# DAC_Board_TOP.net
KiCad netlist of a schematic drawn in Altium Designer
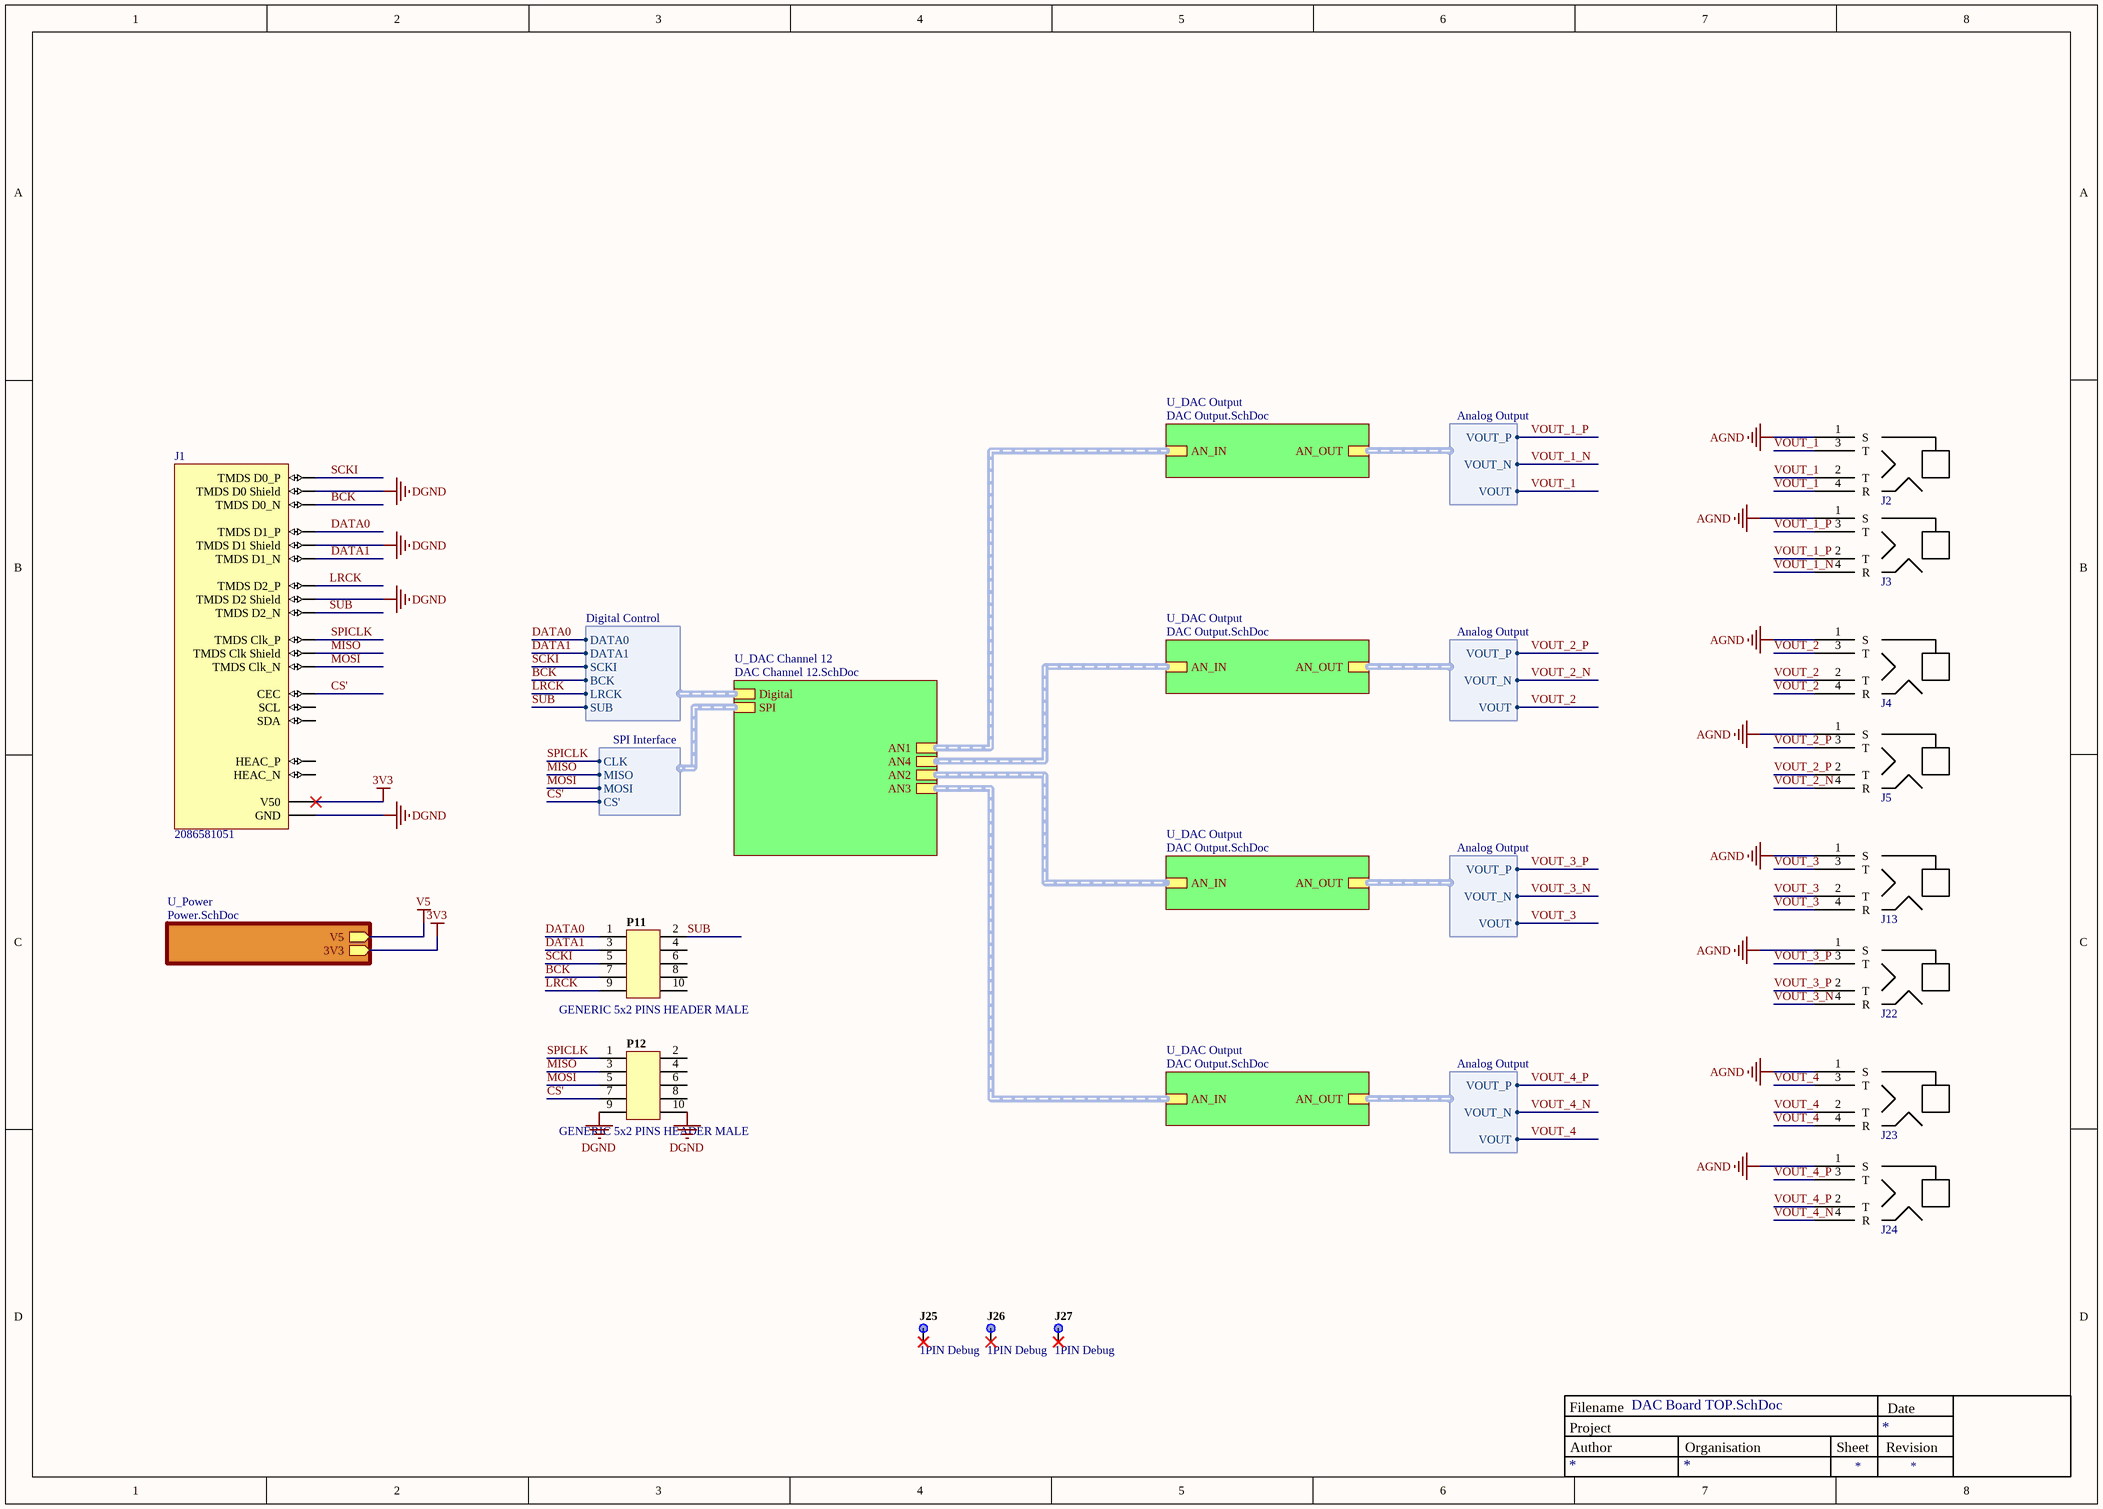
[diagram p0: DAC Board TOP.SchDoc]

(export (version "E")
  (design (tool "Eeschema 10.0.6"))
  (components
    (comp (ref "J1")
      (value "2086581051")
      (footprint "2086581051")
      (description "CONN FEM SMD 19 90Deg HDMI")
      (fields (field (name "DESIGN ITEM ID") "2086581051") (field (name "MANUFACTURER") "Molex"))
      (libsource (lib "University of Malta - MEMENTO") (part "Symbol"))
    )
    (comp (ref "J2")
      (value "SJ1-2503A")
      (footprint "SJ1-2503A-Footprint-1")
      (description "CONN JACK STEREO 2.5MM R/A")
      (libsource (lib "University of Malta - MEMENTO") (part "SJ1-2503A"))
    )
    (comp (ref "J3")
      (value "SJ1-2503A")
      (footprint "SJ1-2503A-Footprint-1")
      (description "CONN JACK STEREO 2.5MM R/A")
      (libsource (lib "University of Malta - MEMENTO") (part "SJ1-2503A"))
    )
    (comp (ref "J4")
      (value "SJ1-2503A")
      (footprint "SJ1-2503A-Footprint-1")
      (description "CONN JACK STEREO 2.5MM R/A")
      (libsource (lib "University of Malta - MEMENTO") (part "SJ1-2503A"))
    )
    (comp (ref "J5")
      (value "SJ1-2503A")
      (footprint "SJ1-2503A-Footprint-1")
      (description "CONN JACK STEREO 2.5MM R/A")
      (libsource (lib "University of Malta - MEMENTO") (part "SJ1-2503A"))
    )
    (comp (ref "J13")
      (value "SJ1-2503A")
      (footprint "SJ1-2503A-Footprint-1")
      (description "CONN JACK STEREO 2.5MM R/A")
      (libsource (lib "University of Malta - MEMENTO") (part "SJ1-2503A"))
    )
    (comp (ref "J22")
      (value "SJ1-2503A")
      (footprint "SJ1-2503A-Footprint-1")
      (description "CONN JACK STEREO 2.5MM R/A")
      (libsource (lib "University of Malta - MEMENTO") (part "SJ1-2503A"))
    )
    (comp (ref "J23")
      (value "SJ1-2503A")
      (footprint "SJ1-2503A-Footprint-1")
      (description "CONN JACK STEREO 2.5MM R/A")
      (libsource (lib "University of Malta - MEMENTO") (part "SJ1-2503A"))
    )
    (comp (ref "J24")
      (value "SJ1-2503A")
      (footprint "SJ1-2503A-Footprint-1")
      (description "CONN JACK STEREO 2.5MM R/A")
      (libsource (lib "University of Malta - MEMENTO") (part "SJ1-2503A"))
    )
    (comp (ref "J25")
      (value "1PIN Debug")
      (footprint "1 Pin Debug Port 0.9mm")
      (description "CONN MAL TH 1 0Deg HEADER")
      (fields (field (name "DESIGN ITEM ID") "1PIN Debug"))
      (libsource (lib "University of Malta - MEMENTO") (part "1PIN Debug"))
    )
    (comp (ref "J26")
      (value "1PIN Debug")
      (footprint "1 Pin Debug Port 0.9mm")
      (description "CONN MAL TH 1 0Deg HEADER")
      (fields (field (name "DESIGN ITEM ID") "1PIN Debug"))
      (libsource (lib "University of Malta - MEMENTO") (part "1PIN Debug"))
    )
    (comp (ref "J27")
      (value "1PIN Debug")
      (footprint "1 Pin Debug Port 0.9mm")
      (description "CONN MAL TH 1 0Deg HEADER")
      (fields (field (name "DESIGN ITEM ID") "1PIN Debug"))
      (libsource (lib "University of Malta - MEMENTO") (part "1PIN Debug"))
    )
    (comp (ref "P11")
      (value "GENERIC 5x2 PINS HEADER MALE")
      (footprint "GENERIC 5PIN 2ROW HEADER 0")
      (description "CONN MAL TH 5x2 0Deg HEADER")
      (fields
        (field (name "DESIGN ITEM ID") "GENERIC 5x2 PINS HEADER MALE")
        (field (name "MANUFACTURER") "Generic")
      )
      (libsource (lib "University of Malta - MEMENTO") (part "GENERIC 5x2 PINS HEADER MALE"))
    )
    (comp (ref "P12")
      (value "GENERIC 5x2 PINS HEADER MALE")
      (footprint "GENERIC 5PIN 2ROW HEADER 0")
      (description "CONN MAL TH 5x2 0Deg HEADER")
      (fields
        (field (name "DESIGN ITEM ID") "GENERIC 5x2 PINS HEADER MALE")
        (field (name "MANUFACTURER") "Generic")
      )
      (libsource (lib "University of Malta - MEMENTO") (part "GENERIC 5x2 PINS HEADER MALE"))
    )
  )
  (nets
    (net (code "11") (name "/BCK") (class "Default")
      (node (ref "J1") (pin "9") (pinfunction "TMDS_D0_N_9") (pintype "bidirectional"))
      (node (ref "P11") (pin "7") (pinfunction "7_7") (pintype "passive"))
    )
    (net (code "12") (name "/CS'") (class "Default")
      (node (ref "J1") (pin "13") (pinfunction "CEC_13") (pintype "bidirectional"))
      (node (ref "P12") (pin "7") (pinfunction "7_7") (pintype "passive"))
    )
    (net (code "13") (name "/DATA0") (class "Default")
      (node (ref "J1") (pin "4") (pinfunction "TMDS_D1_P_4") (pintype "bidirectional"))
      (node (ref "P11") (pin "1") (pinfunction "1_1") (pintype "passive"))
    )
    (net (code "14") (name "/DATA1") (class "Default")
      (node (ref "J1") (pin "6") (pinfunction "TMDS_D1_N_6") (pintype "bidirectional"))
      (node (ref "P11") (pin "3") (pinfunction "3_3") (pintype "passive"))
    )
    (net (code "15") (name "/LRCK") (class "Default")
      (node (ref "J1") (pin "1") (pinfunction "TMDS_D2_P_1") (pintype "bidirectional"))
      (node (ref "P11") (pin "9") (pinfunction "9_9") (pintype "passive"))
    )
    (net (code "16") (name "/MISO") (class "Default")
      (node (ref "J1") (pin "11") (pinfunction "TMDS_Clk_Shield_11") (pintype "bidirectional"))
      (node (ref "P12") (pin "3") (pinfunction "3_3") (pintype "passive"))
    )
    (net (code "17") (name "/MOSI") (class "Default")
      (node (ref "J1") (pin "12") (pinfunction "TMDS_Clk_N_12") (pintype "bidirectional"))
      (node (ref "P12") (pin "5") (pinfunction "5_5") (pintype "passive"))
    )
    (net (code "18") (name "/SCKI") (class "Default")
      (node (ref "J1") (pin "7") (pinfunction "TMDS_D0_P_7") (pintype "bidirectional"))
      (node (ref "P11") (pin "5") (pinfunction "5_5") (pintype "passive"))
    )
    (net (code "19") (name "/SPICLK") (class "Default")
      (node (ref "J1") (pin "10") (pinfunction "TMDS_Clk_P_10") (pintype "bidirectional"))
      (node (ref "P12") (pin "1") (pinfunction "1_1") (pintype "passive"))
    )
    (net (code "20") (name "/SUB") (class "Default")
      (node (ref "J1") (pin "3") (pinfunction "TMDS_D2_N_3") (pintype "bidirectional"))
      (node (ref "P11") (pin "2") (pinfunction "2_2") (pintype "passive"))
    )
    (net (code "21") (name "/VOUT_1") (class "Default")
      (node (ref "J2") (pin "2") (pinfunction "T_2") (pintype "passive"))
      (node (ref "J2") (pin "3") (pinfunction "T_3") (pintype "passive"))
      (node (ref "J2") (pin "4") (pinfunction "R_4") (pintype "passive"))
    )
    (net (code "22") (name "/VOUT_1_N") (class "Default")
      (node (ref "J3") (pin "4") (pinfunction "R_4") (pintype "passive"))
    )
    (net (code "23") (name "/VOUT_1_P") (class "Default")
      (node (ref "J3") (pin "2") (pinfunction "T_2") (pintype "passive"))
      (node (ref "J3") (pin "3") (pinfunction "T_3") (pintype "passive"))
    )
    (net (code "24") (name "/VOUT_2") (class "Default")
      (node (ref "J4") (pin "2") (pinfunction "T_2") (pintype "passive"))
      (node (ref "J4") (pin "3") (pinfunction "T_3") (pintype "passive"))
      (node (ref "J4") (pin "4") (pinfunction "R_4") (pintype "passive"))
    )
    (net (code "25") (name "/VOUT_2_N") (class "Default")
      (node (ref "J5") (pin "4") (pinfunction "R_4") (pintype "passive"))
    )
    (net (code "26") (name "/VOUT_2_P") (class "Default")
      (node (ref "J5") (pin "2") (pinfunction "T_2") (pintype "passive"))
      (node (ref "J5") (pin "3") (pinfunction "T_3") (pintype "passive"))
    )
    (net (code "27") (name "/VOUT_3") (class "Default")
      (node (ref "J13") (pin "2") (pinfunction "T_2") (pintype "passive"))
      (node (ref "J13") (pin "3") (pinfunction "T_3") (pintype "passive"))
      (node (ref "J13") (pin "4") (pinfunction "R_4") (pintype "passive"))
    )
    (net (code "28") (name "/VOUT_3_N") (class "Default")
      (node (ref "J22") (pin "4") (pinfunction "R_4") (pintype "passive"))
    )
    (net (code "29") (name "/VOUT_3_P") (class "Default")
      (node (ref "J22") (pin "2") (pinfunction "T_2") (pintype "passive"))
      (node (ref "J22") (pin "3") (pinfunction "T_3") (pintype "passive"))
    )
    (net (code "30") (name "/VOUT_4") (class "Default")
      (node (ref "J23") (pin "2") (pinfunction "T_2") (pintype "passive"))
      (node (ref "J23") (pin "3") (pinfunction "T_3") (pintype "passive"))
      (node (ref "J23") (pin "4") (pinfunction "R_4") (pintype "passive"))
    )
    (net (code "31") (name "/VOUT_4_N") (class "Default")
      (node (ref "J24") (pin "4") (pinfunction "R_4") (pintype "passive"))
    )
    (net (code "32") (name "/VOUT_4_P") (class "Default")
      (node (ref "J24") (pin "2") (pinfunction "T_2") (pintype "passive"))
      (node (ref "J24") (pin "3") (pinfunction "T_3") (pintype "passive"))
    )
    (net (code "36") (name "3V3") (class "Default")
      (node (ref "J1") (pin "18") (pinfunction "V50_18") (pintype "power_in"))
    )
    (net (code "37") (name "AGND") (class "Default")
      (node (ref "J13") (pin "1") (pinfunction "S_1") (pintype "passive"))
      (node (ref "J2") (pin "1") (pinfunction "S_1") (pintype "passive"))
      (node (ref "J22") (pin "1") (pinfunction "S_1") (pintype "passive"))
      (node (ref "J23") (pin "1") (pinfunction "S_1") (pintype "passive"))
      (node (ref "J24") (pin "1") (pinfunction "S_1") (pintype "passive"))
      (node (ref "J3") (pin "1") (pinfunction "S_1") (pintype "passive"))
      (node (ref "J4") (pin "1") (pinfunction "S_1") (pintype "passive"))
      (node (ref "J5") (pin "1") (pinfunction "S_1") (pintype "passive"))
    )
    (net (code "38") (name "DGND") (class "Default")
      (node (ref "J1") (pin "17") (pinfunction "GND_17") (pintype "power_in"))
      (node (ref "J1") (pin "2") (pinfunction "TMDS_D2_Shield_2") (pintype "bidirectional"))
      (node (ref "J1") (pin "5") (pinfunction "TMDS_D1_Shield_5") (pintype "bidirectional"))
      (node (ref "J1") (pin "8") (pinfunction "TMDS_D0_Shield_8") (pintype "bidirectional"))
      (node (ref "P12") (pin "10") (pinfunction "10_10") (pintype "passive"))
      (node (ref "P12") (pin "9") (pinfunction "9_9") (pintype "passive"))
    )
    (net (code "40") (name "unconnected-(J1-HEAC_N-Pad19)") (class "Default")
      (node (ref "J1") (pin "19") (pinfunction "HEAC_N_19") (pintype "bidirectional"))
    )
    (net (code "41") (name "unconnected-(J1-HEAC_P-Pad14)") (class "Default")
      (node (ref "J1") (pin "14") (pinfunction "HEAC_P_14") (pintype "bidirectional"))
    )
    (net (code "42") (name "unconnected-(J1-SCL-Pad15)") (class "Default")
      (node (ref "J1") (pin "15") (pinfunction "SCL_15") (pintype "bidirectional"))
    )
    (net (code "43") (name "unconnected-(J1-SDA-Pad16)") (class "Default")
      (node (ref "J1") (pin "16") (pinfunction "SDA_16") (pintype "bidirectional"))
    )
    (net (code "44") (name "unconnected-(J25-Pad1)") (class "Default")
      (node (ref "J25") (pin "1") (pinfunction "1_1") (pintype "passive+no_connect"))
    )
    (net (code "45") (name "unconnected-(J26-Pad1)") (class "Default")
      (node (ref "J26") (pin "1") (pinfunction "1_1") (pintype "passive+no_connect"))
    )
    (net (code "46") (name "unconnected-(J27-Pad1)") (class "Default")
      (node (ref "J27") (pin "1") (pinfunction "1_1") (pintype "passive+no_connect"))
    )
    (net (code "47") (name "unconnected-(P11-Pad4)") (class "Default")
      (node (ref "P11") (pin "4") (pinfunction "4_4") (pintype "passive"))
    )
    (net (code "48") (name "unconnected-(P11-Pad6)") (class "Default")
      (node (ref "P11") (pin "6") (pinfunction "6_6") (pintype "passive"))
    )
    (net (code "49") (name "unconnected-(P11-Pad8)") (class "Default")
      (node (ref "P11") (pin "8") (pinfunction "8_8") (pintype "passive"))
    )
    (net (code "50") (name "unconnected-(P11-Pad10)") (class "Default")
      (node (ref "P11") (pin "10") (pinfunction "10_10") (pintype "passive"))
    )
    (net (code "51") (name "unconnected-(P12-Pad2)") (class "Default")
      (node (ref "P12") (pin "2") (pinfunction "2_2") (pintype "passive"))
    )
    (net (code "52") (name "unconnected-(P12-Pad4)") (class "Default")
      (node (ref "P12") (pin "4") (pinfunction "4_4") (pintype "passive"))
    )
    (net (code "53") (name "unconnected-(P12-Pad6)") (class "Default")
      (node (ref "P12") (pin "6") (pinfunction "6_6") (pintype "passive"))
    )
    (net (code "54") (name "unconnected-(P12-Pad8)") (class "Default")
      (node (ref "P12") (pin "8") (pinfunction "8_8") (pintype "passive"))
    )
  )
)
